# Microcontroller.net
KiCad netlist of a schematic drawn in Altium Designer
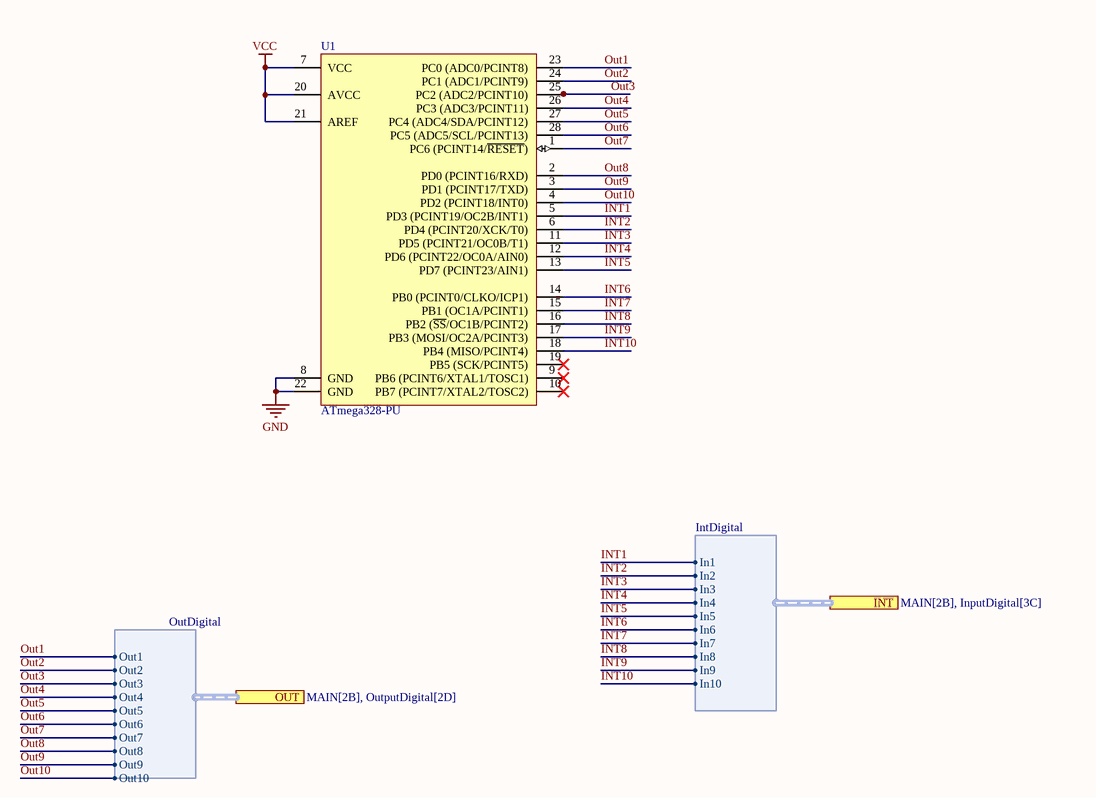
[diagram p0: Microcontroller.SchDoc]

(export (version "E")
  (design (tool "Eeschema 10.0.6"))
  (components
    (comp (ref "U1")
      (value "ATmega328-PU")
      (footprint "28P3")
      (libsource (lib "Ejemplo2") (part "CMP-0095-00015-2"))
    )
  )
  (nets
    (net (code "3") (name "/INT1") (class "Default")
      (node (ref "U1") (pin "5") (pinfunction "PD3_(PCINT19/OC2B/INT1)_5") (pintype "passive"))
    )
    (net (code "4") (name "/INT2") (class "Default")
      (node (ref "U1") (pin "6") (pinfunction "PD4_(PCINT20/XCK/T0)_6") (pintype "passive"))
    )
    (net (code "5") (name "/INT3") (class "Default")
      (node (ref "U1") (pin "11") (pinfunction "PD5_(PCINT21/OC0B/T1)_11") (pintype "passive"))
    )
    (net (code "6") (name "/INT4") (class "Default")
      (node (ref "U1") (pin "12") (pinfunction "PD6_(PCINT22/OC0A/AIN0)_12") (pintype "passive"))
    )
    (net (code "7") (name "/INT5") (class "Default")
      (node (ref "U1") (pin "13") (pinfunction "PD7_(PCINT23/AIN1)_13") (pintype "passive"))
    )
    (net (code "8") (name "/INT6") (class "Default")
      (node (ref "U1") (pin "14") (pinfunction "PB0_(PCINT0/CLKO/ICP1)_14") (pintype "passive"))
    )
    (net (code "9") (name "/INT7") (class "Default")
      (node (ref "U1") (pin "15") (pinfunction "PB1_(OC1A/PCINT1)_15") (pintype "passive"))
    )
    (net (code "10") (name "/INT8") (class "Default")
      (node (ref "U1") (pin "16") (pinfunction "PB2_(~{SS}/OC1B/PCINT2)_16") (pintype "passive"))
    )
    (net (code "11") (name "/INT9") (class "Default")
      (node (ref "U1") (pin "17") (pinfunction "PB3_(MOSI/OC2A/PCINT3)_17") (pintype "passive"))
    )
    (net (code "12") (name "/INT10") (class "Default")
      (node (ref "U1") (pin "18") (pinfunction "PB4_(MISO/PCINT4)_18") (pintype "passive"))
    )
    (net (code "13") (name "/Out1") (class "Default")
      (node (ref "U1") (pin "23") (pinfunction "PC0_(ADC0/PCINT8)_23") (pintype "passive"))
    )
    (net (code "14") (name "/Out2") (class "Default")
      (node (ref "U1") (pin "24") (pinfunction "PC1_(ADC1/PCINT9)_24") (pintype "passive"))
    )
    (net (code "15") (name "/Out3") (class "Default")
      (node (ref "U1") (pin "25") (pinfunction "PC2_(ADC2/PCINT10)_25") (pintype "passive"))
    )
    (net (code "16") (name "/Out4") (class "Default")
      (node (ref "U1") (pin "26") (pinfunction "PC3_(ADC3/PCINT11)_26") (pintype "passive"))
    )
    (net (code "17") (name "/Out5") (class "Default")
      (node (ref "U1") (pin "27") (pinfunction "PC4_(ADC4/SDA/PCINT12)_27") (pintype "passive"))
    )
    (net (code "18") (name "/Out6") (class "Default")
      (node (ref "U1") (pin "28") (pinfunction "PC5_(ADC5/SCL/PCINT13)_28") (pintype "passive"))
    )
    (net (code "19") (name "/Out7") (class "Default")
      (node (ref "U1") (pin "1") (pinfunction "PC6_(PCINT14/~{RESET})_1") (pintype "bidirectional"))
    )
    (net (code "20") (name "/Out8") (class "Default")
      (node (ref "U1") (pin "2") (pinfunction "PD0_(PCINT16/RXD)_2") (pintype "passive"))
    )
    (net (code "21") (name "/Out9") (class "Default")
      (node (ref "U1") (pin "3") (pinfunction "PD1_(PCINT17/TXD)_3") (pintype "passive"))
    )
    (net (code "22") (name "/Out10") (class "Default")
      (node (ref "U1") (pin "4") (pinfunction "PD2_(PCINT18/INT0)_4") (pintype "passive"))
    )
    (net (code "25") (name "GND") (class "Default")
      (node (ref "U1") (pin "22") (pinfunction "GND_22") (pintype "power_in"))
      (node (ref "U1") (pin "8") (pinfunction "GND_8") (pintype "power_in"))
    )
    (net (code "26") (name "VCC") (class "Default")
      (node (ref "U1") (pin "20") (pinfunction "AVCC_20") (pintype "power_in"))
      (node (ref "U1") (pin "21") (pinfunction "AREF_21") (pintype "power_in"))
      (node (ref "U1") (pin "7") (pinfunction "VCC_7") (pintype "power_in"))
    )
    (net (code "27") (name "unconnected-(U1-PB5_(SCK{slash}PCINT5)-Pad19)") (class "Default")
      (node (ref "U1") (pin "19") (pinfunction "PB5_(SCK/PCINT5)_19") (pintype "passive+no_connect"))
    )
    (net (code "28") (name "unconnected-(U1-PB6_(PCINT6{slash}XTAL1{slash}TOSC1)-Pad9)") (class "Default")
      (node (ref "U1") (pin "9") (pinfunction "PB6_(PCINT6/XTAL1/TOSC1)_9") (pintype "passive+no_connect"))
    )
    (net (code "29") (name "unconnected-(U1-PB7_(PCINT7{slash}XTAL2{slash}TOSC2)-Pad10)") (class "Default")
      (node (ref "U1") (pin "10") (pinfunction "PB7_(PCINT7/XTAL2/TOSC2)_10") (pintype "passive+no_connect"))
    )
  )
)
